# Engine_Room_v3.net
KiCad netlist of a schematic drawn in EAGLE
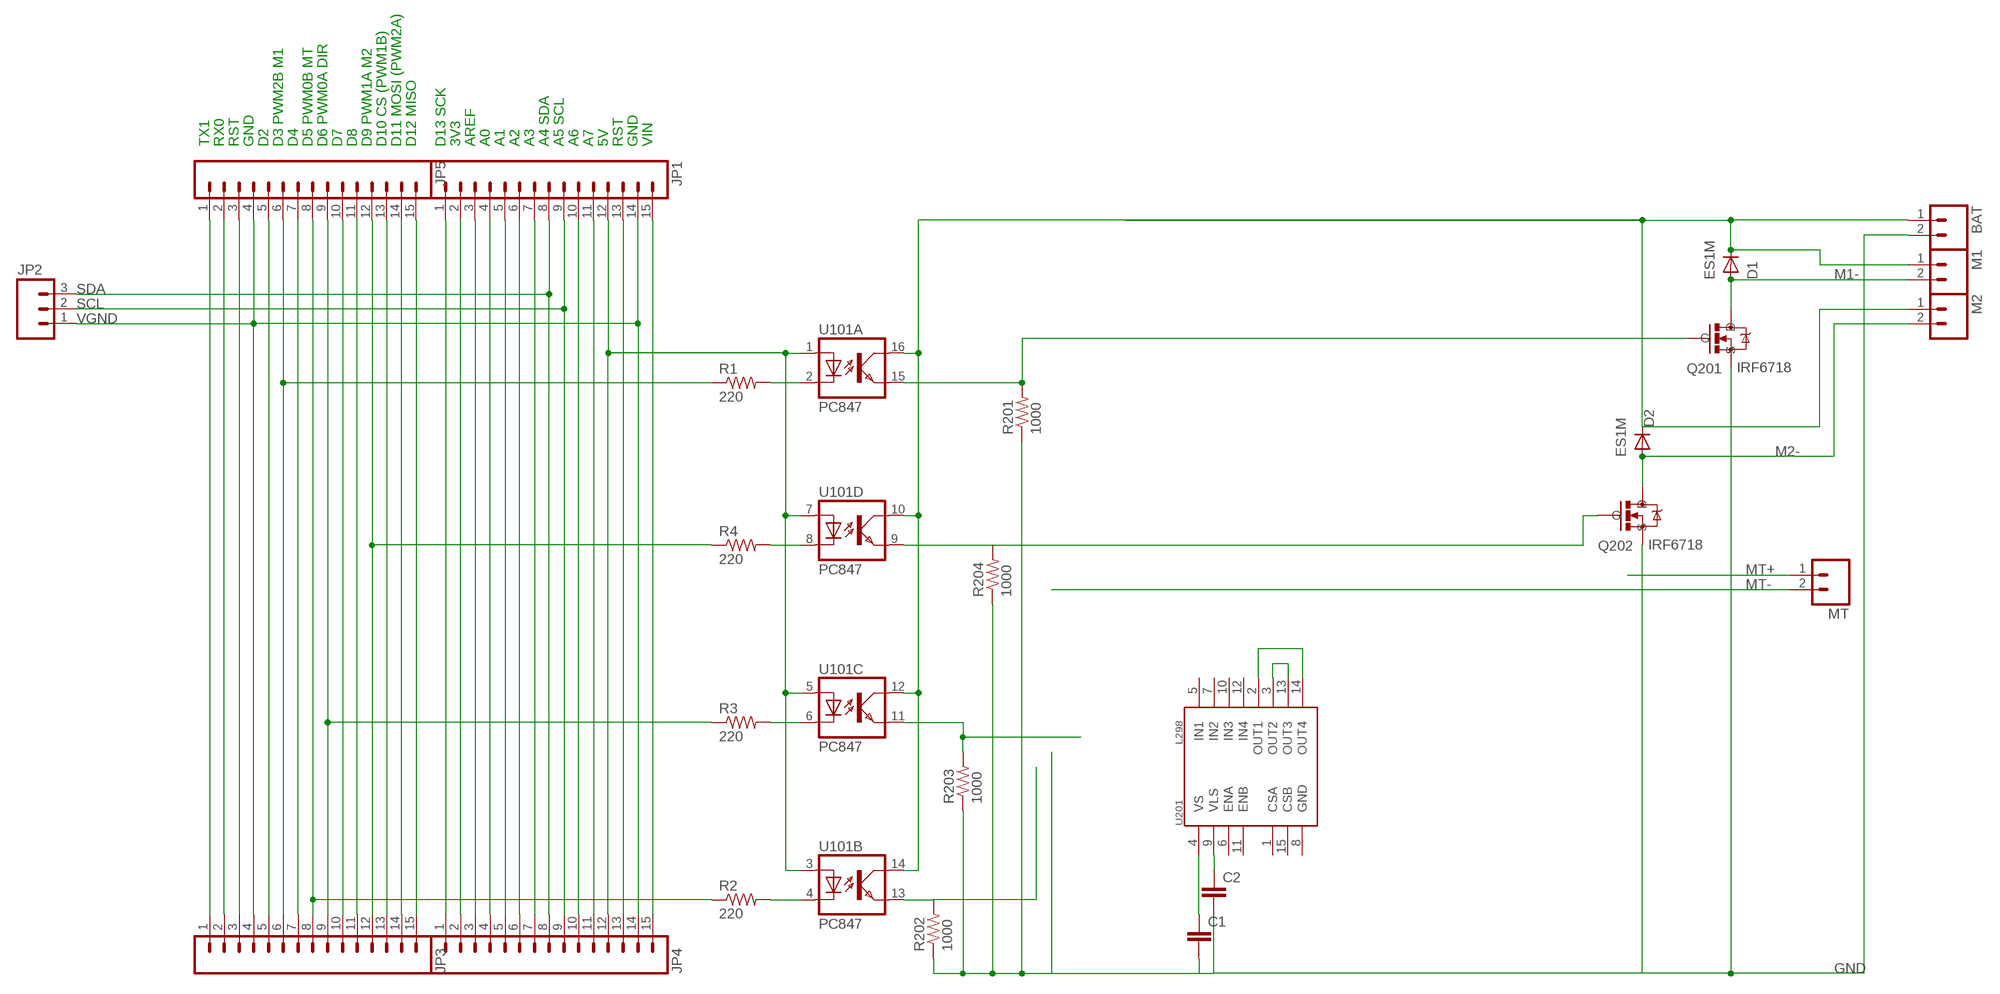
[diagram p0: schematic, sheet 1]

(export (version "E")
  (design (tool "Eeschema 10.0.6"))
  (components
    (comp (ref "BAT")
      (value "M02PTH4")
      (footprint "eagle-import:1X02_XTRA_BIG")
      (libsource (lib "eagle-import") (part "M02PTH4"))
    )
    (comp (ref "C1")
      (value "CAP0402-CAP")
      (footprint "eagle-import:0402-CAP")
      (libsource (lib "eagle-import") (part "CAP0402-CAP"))
    )
    (comp (ref "C2")
      (value "CAP0402-CAP")
      (footprint "eagle-import:0402-CAP")
      (libsource (lib "eagle-import") (part "CAP0402-CAP"))
    )
    (comp (ref "D1")
      (value "ES1M")
      (footprint "eagle-import:DO-214AC")
      (libsource (lib "eagle-import") (part "DIODE-DO-214AC"))
    )
    (comp (ref "D2")
      (value "ES1M")
      (footprint "eagle-import:DO-214AC")
      (libsource (lib "eagle-import") (part "DIODE-DO-214AC"))
    )
    (comp (ref "JP1")
      (value "M15LOCK")
      (footprint "eagle-import:1X15_LOCK")
      (libsource (lib "eagle-import") (part "M15LOCK"))
    )
    (comp (ref "JP2")
      (value "M03LOCK")
      (footprint "eagle-import:1X03_LOCK")
      (libsource (lib "eagle-import") (part "M03LOCK"))
    )
    (comp (ref "JP3")
      (value "M15")
      (footprint "eagle-import:1X15")
      (libsource (lib "eagle-import") (part "M15"))
    )
    (comp (ref "JP4")
      (value "M15")
      (footprint "eagle-import:1X15")
      (libsource (lib "eagle-import") (part "M15"))
    )
    (comp (ref "JP5")
      (value "M15LOCK")
      (footprint "eagle-import:1X15_LOCK")
      (libsource (lib "eagle-import") (part "M15LOCK"))
    )
    (comp (ref "M1")
      (value "M02PTH4")
      (footprint "eagle-import:1X02_XTRA_BIG")
      (libsource (lib "eagle-import") (part "M02PTH4"))
    )
    (comp (ref "M2")
      (value "M02PTH4")
      (footprint "eagle-import:1X02_XTRA_BIG")
      (libsource (lib "eagle-import") (part "M02PTH4"))
    )
    (comp (ref "MT")
      (value "M02PTH")
      (footprint "eagle-import:1X02")
      (libsource (lib "eagle-import") (part "M02PTH"))
    )
    (comp (ref "Q201")
      (value "IRF6718")
      (footprint "eagle-import:DIRECTFET_L6")
      (libsource (lib "eagle-import") (part "IRF6718"))
    )
    (comp (ref "Q202")
      (value "IRF6718")
      (footprint "eagle-import:DIRECTFET_L6")
      (libsource (lib "eagle-import") (part "IRF6718"))
    )
    (comp (ref "R1")
      (value "220")
      (footprint "eagle-import:0402-RES")
      (libsource (lib "eagle-import") (part "RESISTOR0402-RES"))
    )
    (comp (ref "R2")
      (value "220")
      (footprint "eagle-import:0402-RES")
      (libsource (lib "eagle-import") (part "RESISTOR0402-RES"))
    )
    (comp (ref "R3")
      (value "220")
      (footprint "eagle-import:0402-RES")
      (libsource (lib "eagle-import") (part "RESISTOR0402-RES"))
    )
    (comp (ref "R4")
      (value "220")
      (footprint "eagle-import:0402-RES")
      (libsource (lib "eagle-import") (part "RESISTOR0402-RES"))
    )
    (comp (ref "R201")
      (value "1000")
      (footprint "eagle-import:0402-RES")
      (libsource (lib "eagle-import") (part "RESISTOR0402-RES"))
    )
    (comp (ref "R202")
      (value "1000")
      (footprint "eagle-import:0402-RES")
      (libsource (lib "eagle-import") (part "RESISTOR0402-RES"))
    )
    (comp (ref "R203")
      (value "1000")
      (footprint "eagle-import:0402-RES")
      (libsource (lib "eagle-import") (part "RESISTOR0402-RES"))
    )
    (comp (ref "R204")
      (value "1000")
      (footprint "eagle-import:0402-RES")
      (libsource (lib "eagle-import") (part "RESISTOR0402-RES"))
    )
    (comp (ref "U101")
      (value "PC847")
      (footprint "eagle-import:DIL16")
      (libsource (lib "eagle-import") (part "PC847"))
    )
    (comp (ref "U201")
      (value "L298")
      (footprint "eagle-import:MULTIWATT15")
      (libsource (lib "eagle-import") (part "L298"))
    )
  )
  (nets
    (net (code "1") (name "/GND") (class "Default")
      (node (ref "BAT") (pin "2") (pinfunction "2_2") (pintype "passive"))
      (node (ref "C1") (pin "2") (pinfunction "2_2") (pintype "passive"))
      (node (ref "C2") (pin "2") (pinfunction "2_2") (pintype "passive"))
      (node (ref "Q201") (pin "S") (pinfunction "S_S") (pintype "passive"))
      (node (ref "Q202") (pin "S") (pinfunction "S_S") (pintype "passive"))
      (node (ref "R201") (pin "1") (pinfunction "1_1") (pintype "passive"))
      (node (ref "R202") (pin "1") (pinfunction "1_1") (pintype "passive"))
      (node (ref "R203") (pin "1") (pinfunction "1_1") (pintype "passive"))
      (node (ref "R204") (pin "1") (pinfunction "1_1") (pintype "passive"))
    )
    (net (code "2") (name "/M1-") (class "Default")
      (node (ref "D1") (pin "A") (pinfunction "A_A") (pintype "passive"))
      (node (ref "M1") (pin "2") (pinfunction "2_2") (pintype "passive"))
      (node (ref "Q201") (pin "D1") (pinfunction "D_D1") (pintype "passive"))
      (node (ref "Q201") (pin "D2") (pinfunction "D_D2") (pintype "passive"))
    )
    (net (code "3") (name "/M2-") (class "Default")
      (node (ref "D2") (pin "A") (pinfunction "A_A") (pintype "passive"))
      (node (ref "M2") (pin "2") (pinfunction "2_2") (pintype "passive"))
      (node (ref "Q202") (pin "D1") (pinfunction "D_D1") (pintype "passive"))
      (node (ref "Q202") (pin "D2") (pinfunction "D_D2") (pintype "passive"))
    )
    (net (code "4") (name "/MT+") (class "Default")
      (node (ref "MT") (pin "1") (pinfunction "1_1") (pintype "passive"))
    )
    (net (code "5") (name "/MT-") (class "Default")
      (node (ref "MT") (pin "2") (pinfunction "2_2") (pintype "passive"))
    )
    (net (code "6") (name "/SCL") (class "Default")
      (node (ref "JP1") (pin "9") (pinfunction "9_9") (pintype "passive"))
      (node (ref "JP2") (pin "2") (pinfunction "2_2") (pintype "passive"))
      (node (ref "JP4") (pin "9") (pinfunction "9_9") (pintype "passive"))
    )
    (net (code "7") (name "/SDA") (class "Default")
      (node (ref "JP1") (pin "8") (pinfunction "8_8") (pintype "passive"))
      (node (ref "JP2") (pin "3") (pinfunction "3_3") (pintype "passive"))
      (node (ref "JP4") (pin "8") (pinfunction "8_8") (pintype "passive"))
    )
    (net (code "8") (name "/VGND") (class "Default")
      (node (ref "JP1") (pin "14") (pinfunction "14_14") (pintype "passive"))
      (node (ref "JP2") (pin "1") (pinfunction "1_1") (pintype "passive"))
      (node (ref "JP3") (pin "4") (pinfunction "4_4") (pintype "passive"))
      (node (ref "JP4") (pin "14") (pinfunction "14_14") (pintype "passive"))
      (node (ref "JP5") (pin "4") (pinfunction "4_4") (pintype "passive"))
    )
    (net (code "9") (name "Net-(JP1-Pad1)") (class "Default")
      (node (ref "JP1") (pin "1") (pinfunction "1_1") (pintype "passive"))
      (node (ref "JP4") (pin "1") (pinfunction "1_1") (pintype "passive"))
    )
    (net (code "10") (name "Net-(JP1-Pad2)") (class "Default")
      (node (ref "JP1") (pin "2") (pinfunction "2_2") (pintype "passive"))
      (node (ref "JP4") (pin "2") (pinfunction "2_2") (pintype "passive"))
    )
    (net (code "11") (name "Net-(JP1-Pad3)") (class "Default")
      (node (ref "JP1") (pin "3") (pinfunction "3_3") (pintype "passive"))
      (node (ref "JP4") (pin "3") (pinfunction "3_3") (pintype "passive"))
    )
    (net (code "12") (name "Net-(JP1-Pad4)") (class "Default")
      (node (ref "JP1") (pin "4") (pinfunction "4_4") (pintype "passive"))
      (node (ref "JP4") (pin "4") (pinfunction "4_4") (pintype "passive"))
    )
    (net (code "13") (name "Net-(JP1-Pad5)") (class "Default")
      (node (ref "JP1") (pin "5") (pinfunction "5_5") (pintype "passive"))
      (node (ref "JP4") (pin "5") (pinfunction "5_5") (pintype "passive"))
    )
    (net (code "14") (name "Net-(JP1-Pad6)") (class "Default")
      (node (ref "JP1") (pin "6") (pinfunction "6_6") (pintype "passive"))
      (node (ref "JP4") (pin "6") (pinfunction "6_6") (pintype "passive"))
    )
    (net (code "15") (name "Net-(JP1-Pad7)") (class "Default")
      (node (ref "JP1") (pin "7") (pinfunction "7_7") (pintype "passive"))
      (node (ref "JP4") (pin "7") (pinfunction "7_7") (pintype "passive"))
    )
    (net (code "16") (name "Net-(JP1-Pad10)") (class "Default")
      (node (ref "JP1") (pin "10") (pinfunction "10_10") (pintype "passive"))
      (node (ref "JP4") (pin "10") (pinfunction "10_10") (pintype "passive"))
    )
    (net (code "17") (name "Net-(JP1-Pad11)") (class "Default")
      (node (ref "JP1") (pin "11") (pinfunction "11_11") (pintype "passive"))
      (node (ref "JP4") (pin "11") (pinfunction "11_11") (pintype "passive"))
    )
    (net (code "18") (name "Net-(JP1-Pad13)") (class "Default")
      (node (ref "JP1") (pin "13") (pinfunction "13_13") (pintype "passive"))
      (node (ref "JP4") (pin "13") (pinfunction "13_13") (pintype "passive"))
    )
    (net (code "19") (name "Net-(JP1-Pad15)") (class "Default")
      (node (ref "JP1") (pin "15") (pinfunction "15_15") (pintype "passive"))
      (node (ref "JP4") (pin "15") (pinfunction "15_15") (pintype "passive"))
    )
    (net (code "20") (name "Net-(JP3-Pad1)") (class "Default")
      (node (ref "JP3") (pin "1") (pinfunction "1_1") (pintype "passive"))
      (node (ref "JP5") (pin "1") (pinfunction "1_1") (pintype "passive"))
    )
    (net (code "21") (name "Net-(JP3-Pad2)") (class "Default")
      (node (ref "JP3") (pin "2") (pinfunction "2_2") (pintype "passive"))
      (node (ref "JP5") (pin "2") (pinfunction "2_2") (pintype "passive"))
    )
    (net (code "22") (name "Net-(JP3-Pad3)") (class "Default")
      (node (ref "JP3") (pin "3") (pinfunction "3_3") (pintype "passive"))
      (node (ref "JP5") (pin "3") (pinfunction "3_3") (pintype "passive"))
    )
    (net (code "23") (name "Net-(JP3-Pad5)") (class "Default")
      (node (ref "JP3") (pin "5") (pinfunction "5_5") (pintype "passive"))
      (node (ref "JP5") (pin "5") (pinfunction "5_5") (pintype "passive"))
    )
    (net (code "24") (name "Net-(JP3-Pad6)") (class "Default")
      (node (ref "JP3") (pin "6") (pinfunction "6_6") (pintype "passive"))
      (node (ref "JP5") (pin "6") (pinfunction "6_6") (pintype "passive"))
      (node (ref "R1") (pin "1") (pinfunction "1_1") (pintype "passive"))
    )
    (net (code "25") (name "Net-(JP3-Pad7)") (class "Default")
      (node (ref "JP3") (pin "7") (pinfunction "7_7") (pintype "passive"))
      (node (ref "JP5") (pin "7") (pinfunction "7_7") (pintype "passive"))
    )
    (net (code "26") (name "Net-(JP3-Pad8)") (class "Default")
      (node (ref "JP3") (pin "8") (pinfunction "8_8") (pintype "passive"))
      (node (ref "JP5") (pin "8") (pinfunction "8_8") (pintype "passive"))
      (node (ref "R2") (pin "1") (pinfunction "1_1") (pintype "passive"))
    )
    (net (code "27") (name "Net-(JP3-Pad9)") (class "Default")
      (node (ref "JP3") (pin "9") (pinfunction "9_9") (pintype "passive"))
      (node (ref "JP5") (pin "9") (pinfunction "9_9") (pintype "passive"))
      (node (ref "R3") (pin "1") (pinfunction "1_1") (pintype "passive"))
    )
    (net (code "28") (name "Net-(JP3-Pad10)") (class "Default")
      (node (ref "JP3") (pin "10") (pinfunction "10_10") (pintype "passive"))
      (node (ref "JP5") (pin "10") (pinfunction "10_10") (pintype "passive"))
    )
    (net (code "29") (name "Net-(JP3-Pad11)") (class "Default")
      (node (ref "JP3") (pin "11") (pinfunction "11_11") (pintype "passive"))
      (node (ref "JP5") (pin "11") (pinfunction "11_11") (pintype "passive"))
    )
    (net (code "30") (name "Net-(JP3-Pad12)") (class "Default")
      (node (ref "JP3") (pin "12") (pinfunction "12_12") (pintype "passive"))
      (node (ref "JP5") (pin "12") (pinfunction "12_12") (pintype "passive"))
      (node (ref "R4") (pin "1") (pinfunction "1_1") (pintype "passive"))
    )
    (net (code "31") (name "Net-(JP3-Pad13)") (class "Default")
      (node (ref "JP3") (pin "13") (pinfunction "13_13") (pintype "passive"))
      (node (ref "JP5") (pin "13") (pinfunction "13_13") (pintype "passive"))
    )
    (net (code "32") (name "Net-(JP3-Pad14)") (class "Default")
      (node (ref "JP3") (pin "14") (pinfunction "14_14") (pintype "passive"))
      (node (ref "JP5") (pin "14") (pinfunction "14_14") (pintype "passive"))
    )
    (net (code "33") (name "Net-(JP3-Pad15)") (class "Default")
      (node (ref "JP3") (pin "15") (pinfunction "15_15") (pintype "passive"))
      (node (ref "JP5") (pin "15") (pinfunction "15_15") (pintype "passive"))
    )
    (net (code "34") (name "Net-(U101A-A)") (class "Default")
      (node (ref "JP1") (pin "12") (pinfunction "12_12") (pintype "passive"))
      (node (ref "JP4") (pin "12") (pinfunction "12_12") (pintype "passive"))
      (node (ref "U101") (pin "1") (pinfunction "A_1") (pintype "passive"))
      (node (ref "U101") (pin "3") (pinfunction "A_3") (pintype "passive"))
      (node (ref "U101") (pin "5") (pinfunction "A_5") (pintype "passive"))
      (node (ref "U101") (pin "7") (pinfunction "A_7") (pintype "passive"))
    )
    (net (code "35") (name "Net-(U101A-C)") (class "Default")
      (node (ref "R1") (pin "2") (pinfunction "2_2") (pintype "passive"))
      (node (ref "U101") (pin "2") (pinfunction "C_2") (pintype "passive"))
    )
    (net (code "36") (name "Net-(U101A-COL)") (class "Default")
      (node (ref "BAT") (pin "1") (pinfunction "1_1") (pintype "passive"))
      (node (ref "D1") (pin "C") (pinfunction "C_C") (pintype "passive"))
      (node (ref "D2") (pin "C") (pinfunction "C_C") (pintype "passive"))
      (node (ref "M1") (pin "1") (pinfunction "1_1") (pintype "passive"))
      (node (ref "M2") (pin "1") (pinfunction "1_1") (pintype "passive"))
      (node (ref "U101") (pin "10") (pinfunction "COL_10") (pintype "passive"))
      (node (ref "U101") (pin "12") (pinfunction "COL_12") (pintype "passive"))
      (node (ref "U101") (pin "14") (pinfunction "COL_14") (pintype "passive"))
      (node (ref "U101") (pin "16") (pinfunction "COL_16") (pintype "passive"))
    )
    (net (code "37") (name "Net-(U101A-EMIT)") (class "Default")
      (node (ref "Q201") (pin "G") (pinfunction "G_G") (pintype "passive"))
      (node (ref "R201") (pin "2") (pinfunction "2_2") (pintype "passive"))
      (node (ref "U101") (pin "15") (pinfunction "EMIT_15") (pintype "passive"))
    )
    (net (code "38") (name "Net-(U101B-C)") (class "Default")
      (node (ref "R2") (pin "2") (pinfunction "2_2") (pintype "passive"))
      (node (ref "U101") (pin "4") (pinfunction "C_4") (pintype "passive"))
    )
    (net (code "39") (name "Net-(U101B-EMIT)") (class "Default")
      (node (ref "R202") (pin "2") (pinfunction "2_2") (pintype "passive"))
      (node (ref "U101") (pin "13") (pinfunction "EMIT_13") (pintype "passive"))
    )
    (net (code "40") (name "Net-(U101C-C)") (class "Default")
      (node (ref "R3") (pin "2") (pinfunction "2_2") (pintype "passive"))
      (node (ref "U101") (pin "6") (pinfunction "C_6") (pintype "passive"))
    )
    (net (code "41") (name "Net-(U101C-EMIT)") (class "Default")
      (node (ref "R203") (pin "2") (pinfunction "2_2") (pintype "passive"))
      (node (ref "U101") (pin "11") (pinfunction "EMIT_11") (pintype "passive"))
    )
    (net (code "42") (name "Net-(U101D-C)") (class "Default")
      (node (ref "R4") (pin "2") (pinfunction "2_2") (pintype "passive"))
      (node (ref "U101") (pin "8") (pinfunction "C_8") (pintype "passive"))
    )
    (net (code "43") (name "Net-(U101D-EMIT)") (class "Default")
      (node (ref "Q202") (pin "G") (pinfunction "G_G") (pintype "passive"))
      (node (ref "R204") (pin "2") (pinfunction "2_2") (pintype "passive"))
      (node (ref "U101") (pin "9") (pinfunction "EMIT_9") (pintype "passive"))
    )
    (net (code "44") (name "Net-(U201-OUT1)") (class "Default")
      (node (ref "U201") (pin "14") (pinfunction "OUT4_14") (pintype "bidirectional"))
      (node (ref "U201") (pin "2") (pinfunction "OUT1_2") (pintype "bidirectional"))
    )
    (net (code "45") (name "Net-(U201-OUT2)") (class "Default")
      (node (ref "U201") (pin "13") (pinfunction "OUT3_13") (pintype "bidirectional"))
      (node (ref "U201") (pin "3") (pinfunction "OUT2_3") (pintype "bidirectional"))
    )
    (net (code "46") (name "Net-(U201-VLS)") (class "Default")
      (node (ref "C2") (pin "1") (pinfunction "1_1") (pintype "passive"))
      (node (ref "U201") (pin "9") (pinfunction "VLS_9") (pintype "bidirectional"))
    )
    (net (code "47") (name "Net-(U201-VS)") (class "Default")
      (node (ref "C1") (pin "1") (pinfunction "1_1") (pintype "passive"))
      (node (ref "U201") (pin "4") (pinfunction "VS_4") (pintype "bidirectional"))
    )
    (net (code "48") (name "unconnected-(U201-CSA-Pad1)") (class "Default")
      (node (ref "U201") (pin "1") (pinfunction "CSA_1") (pintype "bidirectional"))
    )
    (net (code "49") (name "unconnected-(U201-CSB-Pad15)") (class "Default")
      (node (ref "U201") (pin "15") (pinfunction "CSB_15") (pintype "bidirectional"))
    )
    (net (code "50") (name "unconnected-(U201-ENA-Pad6)") (class "Default")
      (node (ref "U201") (pin "6") (pinfunction "ENA_6") (pintype "bidirectional"))
    )
    (net (code "51") (name "unconnected-(U201-ENB-Pad11)") (class "Default")
      (node (ref "U201") (pin "11") (pinfunction "ENB_11") (pintype "bidirectional"))
    )
    (net (code "52") (name "unconnected-(U201-GND-Pad8)") (class "Default")
      (node (ref "U201") (pin "8") (pinfunction "GND_8") (pintype "bidirectional"))
    )
    (net (code "53") (name "unconnected-(U201-IN1-Pad5)") (class "Default")
      (node (ref "U201") (pin "5") (pinfunction "IN1_5") (pintype "bidirectional"))
    )
    (net (code "54") (name "unconnected-(U201-IN2-Pad7)") (class "Default")
      (node (ref "U201") (pin "7") (pinfunction "IN2_7") (pintype "bidirectional"))
    )
    (net (code "55") (name "unconnected-(U201-IN3-Pad10)") (class "Default")
      (node (ref "U201") (pin "10") (pinfunction "IN3_10") (pintype "bidirectional"))
    )
    (net (code "56") (name "unconnected-(U201-IN4-Pad12)") (class "Default")
      (node (ref "U201") (pin "12") (pinfunction "IN4_12") (pintype "bidirectional"))
    )
  )
)
